# 13_VIDEO_PORT.net
KiCad netlist of a schematic drawn in Altium Designer
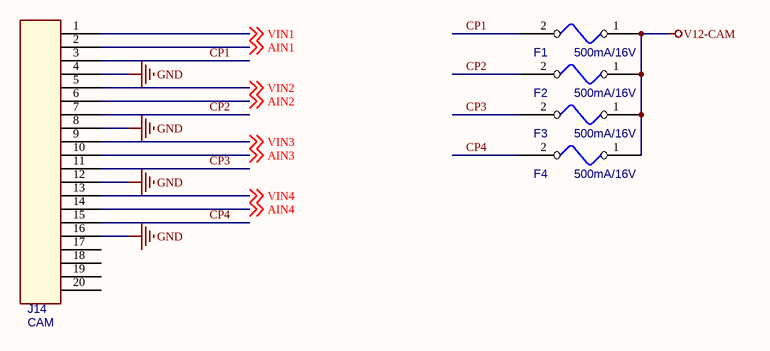
[diagram p0: [13]VIDEO_PORT.SchDoc]

(export (version "E")
  (design (tool "Eeschema 10.0.6"))
  (components
    (comp (ref "F1") (value "500mA/16V") (libsource (lib "*") (part "2A_32VDC_0467-002")))
    (comp (ref "F2") (value "500mA/16V") (libsource (lib "*") (part "2A_32VDC_0467-002")))
    (comp (ref "F3") (value "500mA/16V") (libsource (lib "*") (part "2A_32VDC_0467-002")))
    (comp (ref "F4") (value "500mA/16V") (libsource (lib "*") (part "2A_32VDC_0467-002")))
    (comp (ref "J14") (value "CAM") (libsource (lib "*") (part "CON20")))
  )
  (nets
    (net (code "1") (name "/CP1") (class "Default")
      (node (ref "F1") (pin "2") (pinfunction "2_2") (pintype "passive"))
      (node (ref "J14") (pin "3") (pinfunction "3_3") (pintype "passive"))
    )
    (net (code "2") (name "/CP2") (class "Default")
      (node (ref "F2") (pin "2") (pinfunction "2_2") (pintype "passive"))
      (node (ref "J14") (pin "7") (pinfunction "7_7") (pintype "passive"))
    )
    (net (code "3") (name "/CP3") (class "Default")
      (node (ref "F3") (pin "2") (pinfunction "2_2") (pintype "passive"))
      (node (ref "J14") (pin "11") (pinfunction "11_11") (pintype "passive"))
    )
    (net (code "4") (name "/CP4") (class "Default")
      (node (ref "F4") (pin "2") (pinfunction "2_2") (pintype "passive"))
      (node (ref "J14") (pin "15") (pinfunction "15_15") (pintype "passive"))
    )
    (net (code "5") (name "AIN1") (class "Default")
      (node (ref "J14") (pin "2") (pinfunction "2_2") (pintype "passive"))
    )
    (net (code "6") (name "AIN2") (class "Default")
      (node (ref "J14") (pin "6") (pinfunction "6_6") (pintype "passive"))
    )
    (net (code "7") (name "AIN3") (class "Default")
      (node (ref "J14") (pin "10") (pinfunction "10_10") (pintype "passive"))
    )
    (net (code "8") (name "AIN4") (class "Default")
      (node (ref "J14") (pin "14") (pinfunction "14_14") (pintype "passive"))
    )
    (net (code "9") (name "GND") (class "Default")
      (node (ref "J14") (pin "12") (pinfunction "12_12") (pintype "passive"))
      (node (ref "J14") (pin "16") (pinfunction "16_16") (pintype "passive"))
      (node (ref "J14") (pin "4") (pinfunction "4_4") (pintype "passive"))
      (node (ref "J14") (pin "8") (pinfunction "8_8") (pintype "passive"))
    )
    (net (code "10") (name "V12-CAM") (class "Default")
      (node (ref "F1") (pin "1") (pinfunction "1_1") (pintype "passive"))
      (node (ref "F2") (pin "1") (pinfunction "1_1") (pintype "passive"))
      (node (ref "F3") (pin "1") (pinfunction "1_1") (pintype "passive"))
      (node (ref "F4") (pin "1") (pinfunction "1_1") (pintype "passive"))
    )
    (net (code "11") (name "VIN1") (class "Default")
      (node (ref "J14") (pin "1") (pinfunction "1_1") (pintype "passive"))
    )
    (net (code "12") (name "VIN2") (class "Default")
      (node (ref "J14") (pin "5") (pinfunction "5_5") (pintype "passive"))
    )
    (net (code "13") (name "VIN3") (class "Default")
      (node (ref "J14") (pin "9") (pinfunction "9_9") (pintype "passive"))
    )
    (net (code "14") (name "VIN4") (class "Default")
      (node (ref "J14") (pin "13") (pinfunction "13_13") (pintype "passive"))
    )
    (net (code "15") (name "unconnected-(J14-Pad17)") (class "Default")
      (node (ref "J14") (pin "17") (pinfunction "17_17") (pintype "passive"))
    )
    (net (code "16") (name "unconnected-(J14-Pad18)") (class "Default")
      (node (ref "J14") (pin "18") (pinfunction "18_18") (pintype "passive"))
    )
    (net (code "17") (name "unconnected-(J14-Pad19)") (class "Default")
      (node (ref "J14") (pin "19") (pinfunction "19_19") (pintype "passive"))
    )
    (net (code "18") (name "unconnected-(J14-Pad20)") (class "Default")
      (node (ref "J14") (pin "20") (pinfunction "20_20") (pintype "passive"))
    )
  )
)
